# double_full_wave.net
KiCad netlist of a schematic drawn in EAGLE
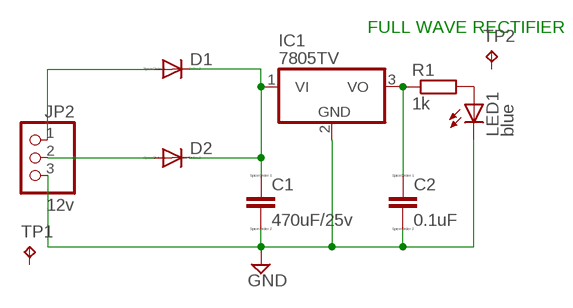
[diagram p0: schematic, sheet 1]

(export (version "E")
  (design (tool "Eeschema 10.0.6"))
  (components
    (comp (ref "C1")
      (value "470uF/25v")
      (footprint "eagle-import:C1206")
      (libsource (lib "eagle-import") (part "CC1206"))
    )
    (comp (ref "C2")
      (value "0.1uF")
      (footprint "eagle-import:C1206")
      (libsource (lib "eagle-import") (part "CC1206"))
    )
    (comp (ref "D1")
      (value "DIODE-SOD323-W")
      (footprint "eagle-import:SOD323-W")
      (libsource (lib "eagle-import") (part "DIODE-SOD323-W"))
    )
    (comp (ref "D2")
      (value "DIODE-SOD323-W")
      (footprint "eagle-import:SOD323-W")
      (libsource (lib "eagle-import") (part "DIODE-SOD323-W"))
    )
    (comp (ref "IC1")
      (value "7805TV")
      (footprint "eagle-import:TO220V")
      (libsource (lib "eagle-import") (part "78TV05"))
    )
    (comp (ref "JP2")
      (value "12v")
      (footprint "eagle-import:1X03")
      (libsource (lib "eagle-import") (part "PINHD-1X3"))
    )
    (comp (ref "LED1")
      (value "blue")
      (footprint "eagle-import:LED5MM")
      (libsource (lib "eagle-import") (part "LED5MM"))
    )
    (comp (ref "R1")
      (value "1k")
      (footprint "eagle-import:M0805")
      (libsource (lib "eagle-import") (part "R-EU_M0805"))
    )
    (comp (ref "TP1")
      (value "TPTP06R")
      (footprint "eagle-import:TP06R")
      (libsource (lib "eagle-import") (part "TPTP06R"))
    )
    (comp (ref "TP2")
      (value "TPTP06R")
      (footprint "eagle-import:TP06R")
      (libsource (lib "eagle-import") (part "TPTP06R"))
    )
  )
  (nets
    (net (code "1") (name "GND") (class "Default")
      (node (ref "C1") (pin "2") (pinfunction "2_2") (pintype "passive"))
      (node (ref "C2") (pin "2") (pinfunction "2_2") (pintype "passive"))
      (node (ref "IC1") (pin "2") (pinfunction "GND_2") (pintype "passive"))
      (node (ref "JP2") (pin "3") (pinfunction "3_3") (pintype "passive"))
      (node (ref "LED1") (pin "K") (pinfunction "C_K") (pintype "passive"))
    )
    (net (code "2") (name "Net-(D1-PadA)") (class "Default")
      (node (ref "D1") (pin "A") (pinfunction "A_A") (pintype "passive"))
      (node (ref "JP2") (pin "1") (pinfunction "1_1") (pintype "passive"))
    )
    (net (code "3") (name "Net-(D2-PadA)") (class "Default")
      (node (ref "D2") (pin "A") (pinfunction "A_A") (pintype "passive"))
      (node (ref "JP2") (pin "2") (pinfunction "2_2") (pintype "passive"))
    )
    (net (code "4") (name "Net-(IC1-VI)") (class "Default")
      (node (ref "C1") (pin "1") (pinfunction "1_1") (pintype "passive"))
      (node (ref "D1") (pin "C") (pinfunction "C_C") (pintype "passive"))
      (node (ref "D2") (pin "C") (pinfunction "C_C") (pintype "passive"))
      (node (ref "IC1") (pin "1") (pinfunction "VI_1") (pintype "input"))
    )
    (net (code "5") (name "Net-(IC1-VO)") (class "Default")
      (node (ref "C2") (pin "1") (pinfunction "1_1") (pintype "passive"))
      (node (ref "IC1") (pin "3") (pinfunction "VO_3") (pintype "passive"))
      (node (ref "R1") (pin "1") (pinfunction "1_1") (pintype "passive"))
    )
    (net (code "6") (name "Net-(LED1-PadA)") (class "Default")
      (node (ref "LED1") (pin "A") (pinfunction "A_A") (pintype "passive"))
      (node (ref "R1") (pin "2") (pinfunction "2_2") (pintype "passive"))
    )
    (net (code "7") (name "unconnected-(TP1-PadTP)") (class "Default")
      (node (ref "TP1") (pin "TP") (pinfunction "TP_TP") (pintype "input"))
    )
    (net (code "8") (name "unconnected-(TP2-PadTP)") (class "Default")
      (node (ref "TP2") (pin "TP") (pinfunction "TP_TP") (pintype "input"))
    )
  )
)
